# ESP32_Board.net
KiCad netlist of a schematic drawn in Altium Designer
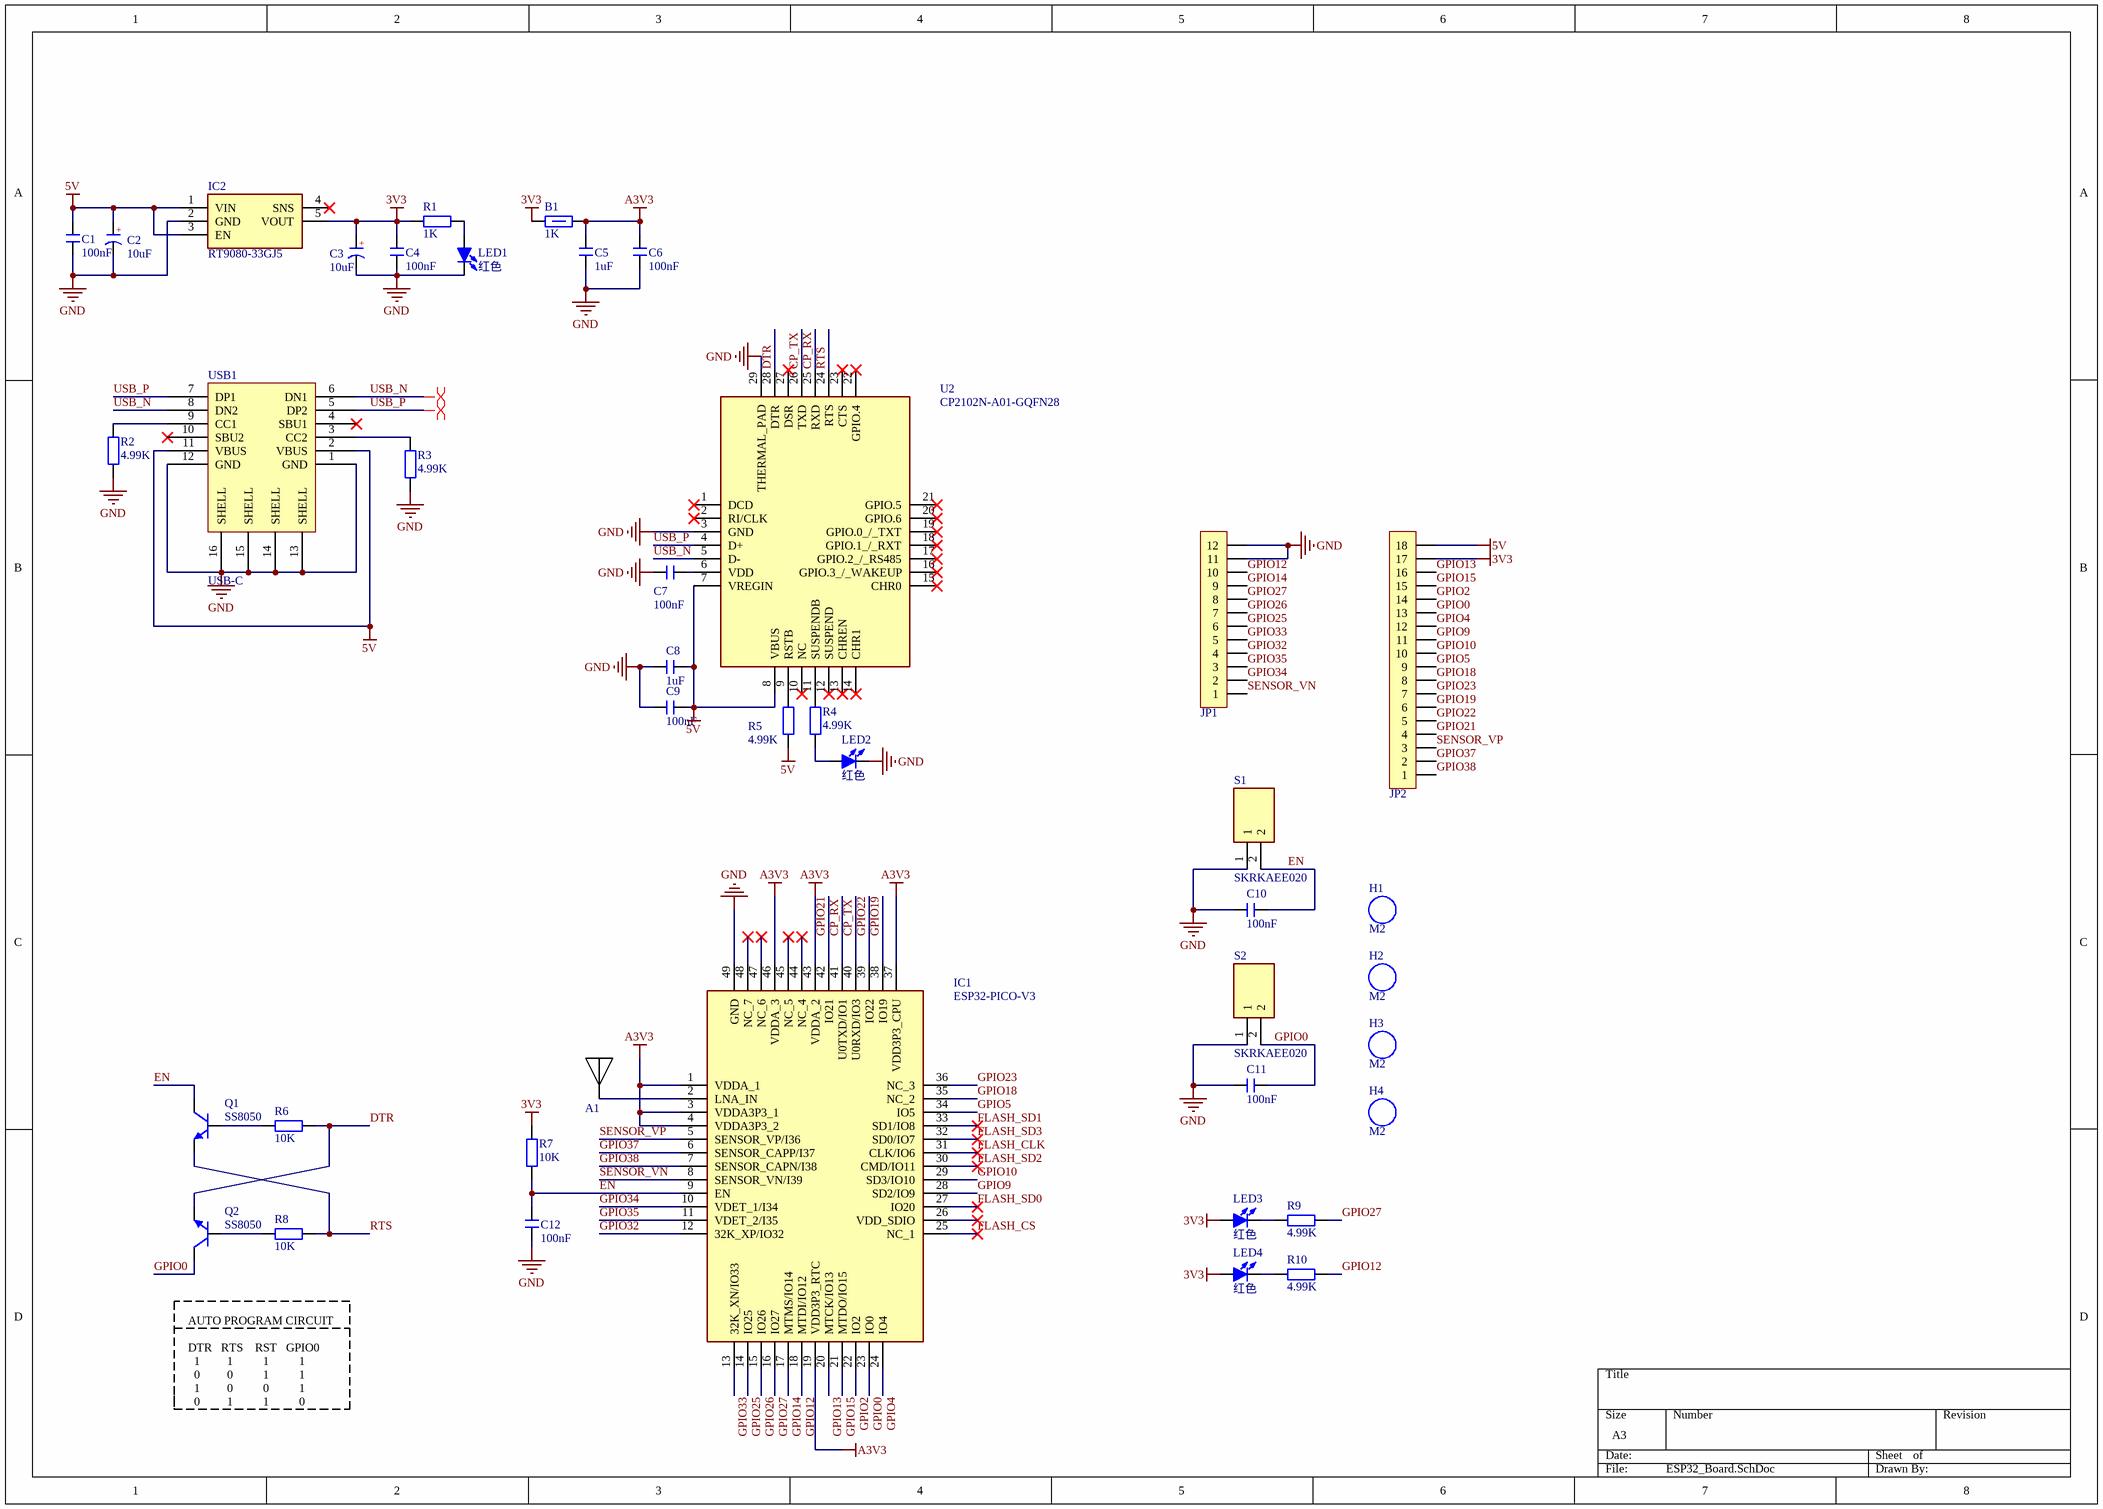
[diagram p0: ESP32_Board.SchDoc]

(export (version "E")
  (design (tool "Eeschema 10.0.6"))
  (components
    (comp (ref "A1")
      (value "RAINSUN")
      (footprint "ANT-Rainsun-AN5120")
      (description "陶瓷天线")
      (libsource (lib "14.1 - 天线") (part "ANT-Rainsun-AP5120"))
    )
    (comp (ref "B1")
      (value "1K")
      (footprint "B 0603_L")
      (description "贴片磁珠")
      (libsource (lib "3.1   - 电阻-电容-电感") (part "B"))
    )
    (comp (ref "C1")
      (value "100nF")
      (footprint "C 0603_L")
      (description "无极性贴片电容")
      (fields (field (name "版权归属") "源创客"))
      (libsource (lib "3.1   - 电阻-电容-电感") (part "C"))
    )
    (comp (ref "C2")
      (value "10uF")
      (footprint "CD A(3216)")
      (description "贴片钽电容")
      (fields (field (name "版权归属") "源创客"))
      (libsource (lib "3.1   - 电阻-电容-电感") (part "C-CD"))
    )
    (comp (ref "C3")
      (value "10uF")
      (footprint "CD A(3216)")
      (description "贴片钽电容")
      (fields (field (name "版权归属") "源创客"))
      (libsource (lib "3.1   - 电阻-电容-电感") (part "C-CD"))
    )
    (comp (ref "C4")
      (value "100nF")
      (footprint "C 0603_L")
      (description "无极性贴片电容")
      (fields (field (name "版权归属") "源创客"))
      (libsource (lib "3.1   - 电阻-电容-电感") (part "C"))
    )
    (comp (ref "C5")
      (value "1uF")
      (footprint "C 0603_L")
      (description "无极性贴片电容")
      (fields (field (name "版权归属") "源创客"))
      (libsource (lib "3.1   - 电阻-电容-电感") (part "C"))
    )
    (comp (ref "C6")
      (value "100nF")
      (footprint "C 0603_L")
      (description "无极性贴片电容")
      (fields (field (name "版权归属") "源创客"))
      (libsource (lib "3.1   - 电阻-电容-电感") (part "C"))
    )
    (comp (ref "C7")
      (value "100nF")
      (footprint "C 0603_L")
      (description "无极性贴片电容")
      (fields (field (name "版权归属") "源创客"))
      (libsource (lib "3.1   - 电阻-电容-电感") (part "C"))
    )
    (comp (ref "C8")
      (value "1uF")
      (footprint "C 0603_L")
      (description "无极性贴片电容")
      (fields (field (name "版权归属") "源创客"))
      (libsource (lib "3.1   - 电阻-电容-电感") (part "C"))
    )
    (comp (ref "C9")
      (value "100nF")
      (footprint "C 0603_L")
      (description "无极性贴片电容")
      (fields (field (name "版权归属") "源创客"))
      (libsource (lib "3.1   - 电阻-电容-电感") (part "C"))
    )
    (comp (ref "C10")
      (value "100nF")
      (footprint "C 0603_L")
      (description "无极性贴片电容")
      (fields (field (name "版权归属") "源创客"))
      (libsource (lib "3.1   - 电阻-电容-电感") (part "C"))
    )
    (comp (ref "C11")
      (value "100nF")
      (footprint "C 0603_L")
      (description "无极性贴片电容")
      (fields (field (name "版权归属") "源创客"))
      (libsource (lib "3.1   - 电阻-电容-电感") (part "C"))
    )
    (comp (ref "C12")
      (value "100nF")
      (footprint "C 0603_L")
      (description "无极性贴片电容")
      (fields (field (name "版权归属") "源创客"))
      (libsource (lib "3.1   - 电阻-电容-电感") (part "C"))
    )
    (comp (ref "H1")
      (value "M2")
      (footprint "M2 - 2.175")
      (description "铜柱孔")
      (fields (field (name "版权归属") "源创客"))
      (libsource (lib "15.1 - 未分类器件") (part "M2"))
    )
    (comp (ref "H2")
      (value "M2")
      (footprint "M2 - 2.175")
      (description "铜柱孔")
      (fields (field (name "版权归属") "源创客"))
      (libsource (lib "15.1 - 未分类器件") (part "M2"))
    )
    (comp (ref "H3")
      (value "M2")
      (footprint "M2 - 2.175")
      (description "铜柱孔")
      (fields (field (name "版权归属") "源创客"))
      (libsource (lib "15.1 - 未分类器件") (part "M2"))
    )
    (comp (ref "H4")
      (value "M2")
      (footprint "M2 - 2.175")
      (description "铜柱孔")
      (fields (field (name "版权归属") "源创客"))
      (libsource (lib "15.1 - 未分类器件") (part "M2"))
    )
    (comp (ref "IC1")
      (value "ESP32-PICO-V3")
      (footprint "SamacSys:ESP32PICOV3")
      (description "Integrated Circuit")
      (fields (field (name "MOUSER PART NUMBER") "356-ESP32-PICO-V3"))
      (libsource (lib "SamacSys") (part "ESP32-PICO-V3"))
    )
    (comp (ref "IC2")
      (value "RT9080-33GJ5")
      (footprint "SamacSys:SOT94P280X100-5N")
      (description "Integrated Circuit")
      (libsource (lib "*") (part "RT9080-33GJ5"))
    )
    (comp (ref "JP1")
      (value "HDR-1X12")
      (footprint "HDR2.54-LI-12P")
      (description "12P接插件")
      (fields (field (name "版权归属") "源创客"))
      (libsource (lib "4.5   - 接插件-脚距2.54") (part "Header 12"))
    )
    (comp (ref "JP2")
      (value "HDR-1X18")
      (footprint "HDR2.54-LI-18P")
      (description "18P接插件")
      (fields (field (name "版权归属") "源创客"))
      (libsource (lib "4.5   - 接插件-脚距2.54") (part "Header 18"))
    )
    (comp (ref "LED1")
      (value "红色")
      (footprint "LED 0603B")
      (description "贴片LED")
      (fields (field (name "版权归属") "源创客"))
      (libsource (lib "9.1   - LED") (part "LED-SMD"))
    )
    (comp (ref "LED2")
      (value "红色")
      (footprint "LED 0603B")
      (description "贴片LED")
      (fields (field (name "版权归属") "源创客"))
      (libsource (lib "9.1   - LED") (part "LED-SMD"))
    )
    (comp (ref "LED3")
      (value "红色")
      (footprint "LED 0603W")
      (description "贴片LED")
      (fields (field (name "版权归属") "源创客"))
      (libsource (lib "9.1   - LED") (part "LED-SMD"))
    )
    (comp (ref "LED4")
      (value "红色")
      (footprint "LED 0603W")
      (description "贴片LED")
      (fields (field (name "版权归属") "源创客"))
      (libsource (lib "9.1   - LED") (part "LED-SMD"))
    )
    (comp (ref "Q1")
      (value "SS8050")
      (footprint "SOT23-3N")
      (description "高频放大-NPN型")
      (fields (field (name "版权归属") "源创客"))
      (libsource (lib "6.2   - 三极管") (part "8050-SMD"))
    )
    (comp (ref "Q2")
      (value "SS8050")
      (footprint "SOT23-3N")
      (description "高频放大-NPN型")
      (fields (field (name "版权归属") "源创客"))
      (libsource (lib "6.2   - 三极管") (part "8050-SMD"))
    )
    (comp (ref "R1")
      (value "1K")
      (footprint "R 0603_L")
      (description "贴片电阻")
      (fields (field (name "版权归属") "源创客"))
      (libsource (lib "3.1   - 电阻-电容-电感") (part "R"))
    )
    (comp (ref "R2")
      (value "4.99K")
      (footprint "R 0603_L")
      (description "贴片电阻")
      (fields (field (name "版权归属") "源创客"))
      (libsource (lib "3.1   - 电阻-电容-电感") (part "R"))
    )
    (comp (ref "R3")
      (value "4.99K")
      (footprint "R 0603_L")
      (description "贴片电阻")
      (fields (field (name "版权归属") "源创客"))
      (libsource (lib "3.1   - 电阻-电容-电感") (part "R"))
    )
    (comp (ref "R4")
      (value "4.99K")
      (footprint "R 0603_L")
      (description "贴片电阻")
      (fields (field (name "版权归属") "源创客"))
      (libsource (lib "3.1   - 电阻-电容-电感") (part "R"))
    )
    (comp (ref "R5")
      (value "4.99K")
      (footprint "R 0603_L")
      (description "贴片电阻")
      (fields (field (name "版权归属") "源创客"))
      (libsource (lib "3.1   - 电阻-电容-电感") (part "R"))
    )
    (comp (ref "R6")
      (value "10K")
      (footprint "R 0603_L")
      (description "贴片电阻")
      (fields (field (name "版权归属") "源创客"))
      (libsource (lib "3.1   - 电阻-电容-电感") (part "R"))
    )
    (comp (ref "R7")
      (value "10K")
      (footprint "R 0603_L")
      (description "贴片电阻")
      (fields (field (name "版权归属") "源创客"))
      (libsource (lib "3.1   - 电阻-电容-电感") (part "R"))
    )
    (comp (ref "R8")
      (value "10K")
      (footprint "R 0603_L")
      (description "贴片电阻")
      (fields (field (name "版权归属") "源创客"))
      (libsource (lib "3.1   - 电阻-电容-电感") (part "R"))
    )
    (comp (ref "R9")
      (value "4.99K")
      (footprint "R 0603_L")
      (description "贴片电阻")
      (fields (field (name "版权归属") "源创客"))
      (libsource (lib "3.1   - 电阻-电容-电感") (part "R"))
    )
    (comp (ref "R10")
      (value "4.99K")
      (footprint "R 0603_L")
      (description "贴片电阻")
      (fields (field (name "版权归属") "源创客"))
      (libsource (lib "3.1   - 电阻-电容-电感") (part "R"))
    )
    (comp (ref "S1")
      (value "SKRKAEE020")
      (footprint "SamacSys:SKRKAEE020")
      (description "Switch")
      (fields (field (name "MOUSER PART NUMBER") "688-SKRKAEE020"))
      (libsource (lib "*") (part "SKRKAEE020"))
    )
    (comp (ref "S2")
      (value "SKRKAEE020")
      (footprint "SamacSys:SKRKAEE020")
      (description "Switch")
      (fields (field (name "MOUSER PART NUMBER") "688-SKRKAEE020"))
      (libsource (lib "*") (part "SKRKAEE020"))
    )
    (comp (ref "U2")
      (value "CP2102N-A01-GQFN28")
      (footprint "QFN28")
      (description "Integrated Circuit")
      (fields (field (name "MOUSER PART NUMBER") "634-CP2102NA01GQFN28"))
      (libsource (lib "*") (part "CP2102N-A01-GQFN28"))
    )
    (comp (ref "USB1")
      (value "USB-C")
      (footprint "USB-C-16")
      (description "USB-C型母接口")
      (fields (field (name "版权归属") "源创客"))
      (libsource (lib "4.1   - 接口类") (part "USB-C/16P"))
    )
  )
  (nets
    (net (code "1") (name "/CP_RX") (class "Default")
      (node (ref "IC1") (pin "41") (pinfunction "U0TXD/IO1_41") (pintype "passive"))
      (node (ref "U2") (pin "25") (pinfunction "RXD_25") (pintype "passive"))
    )
    (net (code "2") (name "/CP_TX") (class "Default")
      (node (ref "IC1") (pin "40") (pinfunction "U0RXD/IO3_40") (pintype "passive"))
      (node (ref "U2") (pin "26") (pinfunction "TXD_26") (pintype "passive"))
    )
    (net (code "3") (name "/DTR") (class "Default")
      (node (ref "Q2") (pin "2") (pinfunction "E_2") (pintype "passive"))
      (node (ref "R6") (pin "1") (pinfunction "1_1") (pintype "passive"))
      (node (ref "U2") (pin "28") (pinfunction "DTR_28") (pintype "passive"))
    )
    (net (code "4") (name "/EN") (class "Default")
      (node (ref "C10") (pin "1") (pinfunction "1_1") (pintype "passive"))
      (node (ref "C12") (pin "2") (pinfunction "2_2") (pintype "passive"))
      (node (ref "IC1") (pin "9") (pinfunction "EN_9") (pintype "passive"))
      (node (ref "Q1") (pin "3") (pinfunction "C_3") (pintype "passive"))
      (node (ref "R7") (pin "2") (pinfunction "2_2") (pintype "passive"))
      (node (ref "S1") (pin "2") (pinfunction "2_2") (pintype "passive"))
    )
    (net (code "5") (name "/FLASH_CLK") (class "Default")
      (node (ref "IC1") (pin "31") (pinfunction "CLK/IO6_31") (pintype "passive+no_connect"))
    )
    (net (code "6") (name "/FLASH_CS") (class "Default")
      (node (ref "IC1") (pin "25") (pinfunction "NC_1_25") (pintype "passive+no_connect"))
    )
    (net (code "7") (name "/FLASH_SD0") (class "Default")
      (node (ref "IC1") (pin "27") (pinfunction "IO20_27") (pintype "passive+no_connect"))
    )
    (net (code "8") (name "/FLASH_SD1") (class "Default")
      (node (ref "IC1") (pin "33") (pinfunction "SD1/IO8_33") (pintype "passive+no_connect"))
    )
    (net (code "9") (name "/FLASH_SD2") (class "Default")
      (node (ref "IC1") (pin "30") (pinfunction "CMD/IO11_30") (pintype "passive+no_connect"))
    )
    (net (code "10") (name "/FLASH_SD3") (class "Default")
      (node (ref "IC1") (pin "32") (pinfunction "SD0/IO7_32") (pintype "passive+no_connect"))
    )
    (net (code "11") (name "/GPIO0") (class "Default")
      (node (ref "C11") (pin "1") (pinfunction "1_1") (pintype "passive"))
      (node (ref "IC1") (pin "23") (pinfunction "IO0_23") (pintype "passive"))
      (node (ref "JP2") (pin "13") (pinfunction "13_13") (pintype "passive"))
      (node (ref "Q2") (pin "3") (pinfunction "C_3") (pintype "passive"))
      (node (ref "S2") (pin "2") (pinfunction "2_2") (pintype "passive"))
    )
    (net (code "12") (name "/GPIO2") (class "Default")
      (node (ref "IC1") (pin "22") (pinfunction "IO2_22") (pintype "passive"))
      (node (ref "JP2") (pin "14") (pinfunction "14_14") (pintype "passive"))
    )
    (net (code "13") (name "/GPIO4") (class "Default")
      (node (ref "IC1") (pin "24") (pinfunction "IO4_24") (pintype "passive"))
      (node (ref "JP2") (pin "12") (pinfunction "12_12") (pintype "passive"))
    )
    (net (code "14") (name "/GPIO5") (class "Default")
      (node (ref "IC1") (pin "34") (pinfunction "IO5_34") (pintype "passive"))
      (node (ref "JP2") (pin "9") (pinfunction "9_9") (pintype "passive"))
    )
    (net (code "15") (name "/GPIO9") (class "Default")
      (node (ref "IC1") (pin "28") (pinfunction "SD2/IO9_28") (pintype "passive"))
      (node (ref "JP2") (pin "11") (pinfunction "11_11") (pintype "passive"))
    )
    (net (code "16") (name "/GPIO10") (class "Default")
      (node (ref "IC1") (pin "29") (pinfunction "SD3/IO10_29") (pintype "passive"))
      (node (ref "JP2") (pin "10") (pinfunction "10_10") (pintype "passive"))
    )
    (net (code "17") (name "/GPIO12") (class "Default")
      (node (ref "IC1") (pin "18") (pinfunction "MTDI/IO12_18") (pintype "passive"))
      (node (ref "JP1") (pin "10") (pinfunction "10_10") (pintype "passive"))
      (node (ref "R10") (pin "1") (pinfunction "1_1") (pintype "passive"))
    )
    (net (code "18") (name "/GPIO13") (class "Default")
      (node (ref "IC1") (pin "20") (pinfunction "MTCK/IO13_20") (pintype "passive"))
      (node (ref "JP2") (pin "16") (pinfunction "16_16") (pintype "passive"))
    )
    (net (code "19") (name "/GPIO14") (class "Default")
      (node (ref "IC1") (pin "17") (pinfunction "MTMS/IO14_17") (pintype "passive"))
      (node (ref "JP1") (pin "9") (pinfunction "9_9") (pintype "passive"))
    )
    (net (code "20") (name "/GPIO15") (class "Default")
      (node (ref "IC1") (pin "21") (pinfunction "MTDO/IO15_21") (pintype "passive"))
      (node (ref "JP2") (pin "15") (pinfunction "15_15") (pintype "passive"))
    )
    (net (code "21") (name "/GPIO18") (class "Default")
      (node (ref "IC1") (pin "35") (pinfunction "NC_2_35") (pintype "passive"))
      (node (ref "JP2") (pin "8") (pinfunction "8_8") (pintype "passive"))
    )
    (net (code "22") (name "/GPIO19") (class "Default")
      (node (ref "IC1") (pin "38") (pinfunction "IO19_38") (pintype "passive"))
      (node (ref "JP2") (pin "6") (pinfunction "6_6") (pintype "passive"))
    )
    (net (code "23") (name "/GPIO21") (class "Default")
      (node (ref "IC1") (pin "42") (pinfunction "IO21_42") (pintype "passive"))
      (node (ref "JP2") (pin "4") (pinfunction "4_4") (pintype "passive"))
    )
    (net (code "24") (name "/GPIO22") (class "Default")
      (node (ref "IC1") (pin "39") (pinfunction "IO22_39") (pintype "passive"))
      (node (ref "JP2") (pin "5") (pinfunction "5_5") (pintype "passive"))
    )
    (net (code "25") (name "/GPIO23") (class "Default")
      (node (ref "IC1") (pin "36") (pinfunction "NC_3_36") (pintype "passive"))
      (node (ref "JP2") (pin "7") (pinfunction "7_7") (pintype "passive"))
    )
    (net (code "26") (name "/GPIO25") (class "Default")
      (node (ref "IC1") (pin "14") (pinfunction "IO25_14") (pintype "passive"))
      (node (ref "JP1") (pin "6") (pinfunction "6_6") (pintype "passive"))
    )
    (net (code "27") (name "/GPIO26") (class "Default")
      (node (ref "IC1") (pin "15") (pinfunction "IO26_15") (pintype "passive"))
      (node (ref "JP1") (pin "7") (pinfunction "7_7") (pintype "passive"))
    )
    (net (code "28") (name "/GPIO27") (class "Default")
      (node (ref "IC1") (pin "16") (pinfunction "IO27_16") (pintype "passive"))
      (node (ref "JP1") (pin "8") (pinfunction "8_8") (pintype "passive"))
      (node (ref "R9") (pin "1") (pinfunction "1_1") (pintype "passive"))
    )
    (net (code "29") (name "/GPIO32") (class "Default")
      (node (ref "IC1") (pin "12") (pinfunction "32K_XP/IO32_12") (pintype "passive"))
      (node (ref "JP1") (pin "4") (pinfunction "4_4") (pintype "passive"))
    )
    (net (code "30") (name "/GPIO33") (class "Default")
      (node (ref "IC1") (pin "13") (pinfunction "32K_XN/IO33_13") (pintype "passive"))
      (node (ref "JP1") (pin "5") (pinfunction "5_5") (pintype "passive"))
    )
    (net (code "31") (name "/GPIO34") (class "Default")
      (node (ref "IC1") (pin "10") (pinfunction "VDET_1/I34_10") (pintype "passive"))
      (node (ref "JP1") (pin "2") (pinfunction "2_2") (pintype "passive"))
    )
    (net (code "32") (name "/GPIO35") (class "Default")
      (node (ref "IC1") (pin "11") (pinfunction "VDET_2/I35_11") (pintype "passive"))
      (node (ref "JP1") (pin "3") (pinfunction "3_3") (pintype "passive"))
    )
    (net (code "33") (name "/GPIO37") (class "Default")
      (node (ref "IC1") (pin "6") (pinfunction "SENSOR_CAPP/I37_6") (pintype "passive"))
      (node (ref "JP2") (pin "2") (pinfunction "2_2") (pintype "passive"))
    )
    (net (code "34") (name "/GPIO38") (class "Default")
      (node (ref "IC1") (pin "7") (pinfunction "SENSOR_CAPN/I38_7") (pintype "passive"))
      (node (ref "JP2") (pin "1") (pinfunction "1_1") (pintype "passive"))
    )
    (net (code "35") (name "/RTS") (class "Default")
      (node (ref "Q1") (pin "2") (pinfunction "E_2") (pintype "passive"))
      (node (ref "R8") (pin "1") (pinfunction "1_1") (pintype "passive"))
      (node (ref "U2") (pin "24") (pinfunction "RTS_24") (pintype "passive"))
    )
    (net (code "36") (name "/SENSOR_VN") (class "Default")
      (node (ref "IC1") (pin "8") (pinfunction "SENSOR_VN/I39_8") (pintype "passive"))
      (node (ref "JP1") (pin "1") (pinfunction "1_1") (pintype "passive"))
    )
    (net (code "37") (name "/SENSOR_VP") (class "Default")
      (node (ref "IC1") (pin "5") (pinfunction "SENSOR_VP/I36_5") (pintype "passive"))
      (node (ref "JP2") (pin "3") (pinfunction "3_3") (pintype "passive"))
    )
    (net (code "38") (name "/USB_N") (class "Default")
      (node (ref "U2") (pin "5") (pinfunction "D-_5") (pintype "passive"))
      (node (ref "USB1") (pin "6") (pinfunction "DN1_6") (pintype "passive"))
      (node (ref "USB1") (pin "8") (pinfunction "DN2_8") (pintype "passive"))
    )
    (net (code "39") (name "/USB_P") (class "Default")
      (node (ref "U2") (pin "4") (pinfunction "D+_4") (pintype "passive"))
      (node (ref "USB1") (pin "5") (pinfunction "DP2_5") (pintype "passive"))
      (node (ref "USB1") (pin "7") (pinfunction "DP1_7") (pintype "passive"))
    )
    (net (code "40") (name "3V3") (class "Default")
      (node (ref "B1") (pin "2") (pinfunction "2_2") (pintype "passive"))
      (node (ref "C3") (pin "1") (pinfunction "A_1") (pintype "passive"))
      (node (ref "C4") (pin "2") (pinfunction "2_2") (pintype "passive"))
      (node (ref "IC2") (pin "5") (pinfunction "VOUT_5") (pintype "passive"))
      (node (ref "JP2") (pin "17") (pinfunction "17_17") (pintype "passive"))
      (node (ref "LED3") (pin "1") (pinfunction "A_1") (pintype "passive"))
      (node (ref "LED4") (pin "1") (pinfunction "A_1") (pintype "passive"))
      (node (ref "R1") (pin "2") (pinfunction "2_2") (pintype "passive"))
      (node (ref "R7") (pin "1") (pinfunction "1_1") (pintype "passive"))
    )
    (net (code "41") (name "5V") (class "Default")
      (node (ref "C1") (pin "2") (pinfunction "2_2") (pintype "passive"))
      (node (ref "C2") (pin "1") (pinfunction "A_1") (pintype "passive"))
      (node (ref "C8") (pin "1") (pinfunction "1_1") (pintype "passive"))
      (node (ref "C9") (pin "1") (pinfunction "1_1") (pintype "passive"))
      (node (ref "IC2") (pin "1") (pinfunction "VIN_1") (pintype "passive"))
      (node (ref "IC2") (pin "3") (pinfunction "EN_3") (pintype "passive"))
      (node (ref "JP2") (pin "18") (pinfunction "18_18") (pintype "passive"))
      (node (ref "R5") (pin "1") (pinfunction "1_1") (pintype "passive"))
      (node (ref "U2") (pin "7") (pinfunction "VREGIN_7") (pintype "passive"))
      (node (ref "U2") (pin "8") (pinfunction "VBUS_8") (pintype "passive"))
      (node (ref "USB1") (pin "11") (pinfunction "VBUS_11") (pintype "passive"))
      (node (ref "USB1") (pin "2") (pinfunction "VBUS_2") (pintype "passive"))
    )
    (net (code "42") (name "A3V3") (class "Default")
      (node (ref "B1") (pin "1") (pinfunction "1_1") (pintype "passive"))
      (node (ref "C5") (pin "2") (pinfunction "2_2") (pintype "passive"))
      (node (ref "C6") (pin "2") (pinfunction "2_2") (pintype "passive"))
      (node (ref "IC1") (pin "1") (pinfunction "VDDA_1_1") (pintype "passive"))
      (node (ref "IC1") (pin "19") (pinfunction "VDD3P3_RTC_19") (pintype "passive"))
      (node (ref "IC1") (pin "3") (pinfunction "VDDA3P3_1_3") (pintype "passive"))
      (node (ref "IC1") (pin "37") (pinfunction "VDD3P3_CPU_37") (pintype "passive"))
      (node (ref "IC1") (pin "4") (pinfunction "VDDA3P3_2_4") (pintype "passive"))
      (node (ref "IC1") (pin "43") (pinfunction "VDDA_2_43") (pintype "passive"))
      (node (ref "IC1") (pin "46") (pinfunction "VDDA_3_46") (pintype "passive"))
    )
    (net (code "43") (name "GND") (class "Default")
      (node (ref "C1") (pin "1") (pinfunction "1_1") (pintype "passive"))
      (node (ref "C10") (pin "2") (pinfunction "2_2") (pintype "passive"))
      (node (ref "C11") (pin "2") (pinfunction "2_2") (pintype "passive"))
      (node (ref "C12") (pin "1") (pinfunction "1_1") (pintype "passive"))
      (node (ref "C2") (pin "2") (pinfunction "K_2") (pintype "passive"))
      (node (ref "C3") (pin "2") (pinfunction "K_2") (pintype "passive"))
      (node (ref "C4") (pin "1") (pinfunction "1_1") (pintype "passive"))
      (node (ref "C5") (pin "1") (pinfunction "1_1") (pintype "passive"))
      (node (ref "C6") (pin "1") (pinfunction "1_1") (pintype "passive"))
      (node (ref "C7") (pin "2") (pinfunction "2_2") (pintype "passive"))
      (node (ref "C8") (pin "2") (pinfunction "2_2") (pintype "passive"))
      (node (ref "C9") (pin "2") (pinfunction "2_2") (pintype "passive"))
      (node (ref "IC1") (pin "49") (pinfunction "GND_49") (pintype "passive"))
      (node (ref "IC2") (pin "2") (pinfunction "GND_2") (pintype "passive"))
      (node (ref "JP1") (pin "11") (pinfunction "11_11") (pintype "passive"))
      (node (ref "JP1") (pin "12") (pinfunction "12_12") (pintype "passive"))
      (node (ref "LED1") (pin "2") (pinfunction "K_2") (pintype "passive"))
      (node (ref "LED2") (pin "2") (pinfunction "K_2") (pintype "passive"))
      (node (ref "R2") (pin "2") (pinfunction "2_2") (pintype "passive"))
      (node (ref "R3") (pin "2") (pinfunction "2_2") (pintype "passive"))
      (node (ref "S1") (pin "1") (pinfunction "1_1") (pintype "passive"))
      (node (ref "S2") (pin "1") (pinfunction "1_1") (pintype "passive"))
      (node (ref "U2") (pin "29") (pinfunction "THERMAL_PAD_29") (pintype "passive"))
      (node (ref "U2") (pin "3") (pinfunction "GND_3") (pintype "passive"))
      (node (ref "USB1") (pin "1") (pinfunction "GND_1") (pintype "passive"))
      (node (ref "USB1") (pin "12") (pinfunction "GND_12") (pintype "passive"))
      (node (ref "USB1") (pin "13") (pinfunction "SHELL_13") (pintype "passive"))
      (node (ref "USB1") (pin "14") (pinfunction "SHELL_14") (pintype "passive"))
      (node (ref "USB1") (pin "15") (pinfunction "SHELL_15") (pintype "passive"))
      (node (ref "USB1") (pin "16") (pinfunction "SHELL_16") (pintype "passive"))
    )
    (net (code "44") (name "Net-(IC1-LNA_IN)") (class "Default")
      (node (ref "A1") (pin "1") (pinfunction "1_1") (pintype "passive"))
      (node (ref "IC1") (pin "2") (pinfunction "LNA_IN_2") (pintype "passive"))
    )
    (net (code "45") (name "Net-(LED1-A)") (class "Default")
      (node (ref "LED1") (pin "1") (pinfunction "A_1") (pintype "passive"))
      (node (ref "R1") (pin "1") (pinfunction "1_1") (pintype "passive"))
    )
    (net (code "46") (name "Net-(LED2-A)") (class "Default")
      (node (ref "LED2") (pin "1") (pinfunction "A_1") (pintype "passive"))
      (node (ref "R4") (pin "1") (pinfunction "1_1") (pintype "passive"))
    )
    (net (code "47") (name "Net-(LED3-K)") (class "Default")
      (node (ref "LED3") (pin "2") (pinfunction "K_2") (pintype "passive"))
      (node (ref "R9") (pin "2") (pinfunction "2_2") (pintype "passive"))
    )
    (net (code "48") (name "Net-(LED4-K)") (class "Default")
      (node (ref "LED4") (pin "2") (pinfunction "K_2") (pintype "passive"))
      (node (ref "R10") (pin "2") (pinfunction "2_2") (pintype "passive"))
    )
    (net (code "49") (name "Net-(Q1-B)") (class "Default")
      (node (ref "Q1") (pin "1") (pinfunction "B_1") (pintype "passive"))
      (node (ref "R6") (pin "2") (pinfunction "2_2") (pintype "passive"))
    )
    (net (code "50") (name "Net-(Q2-B)") (class "Default")
      (node (ref "Q2") (pin "1") (pinfunction "B_1") (pintype "passive"))
      (node (ref "R8") (pin "2") (pinfunction "2_2") (pintype "passive"))
    )
    (net (code "51") (name "Net-(U2-RSTB)") (class "Default")
      (node (ref "R5") (pin "2") (pinfunction "2_2") (pintype "passive"))
      (node (ref "U2") (pin "9") (pinfunction "RSTB_9") (pintype "passive"))
    )
    (net (code "52") (name "Net-(U2-SUSPENDB)") (class "Default")
      (node (ref "R4") (pin "2") (pinfunction "2_2") (pintype "passive"))
      (node (ref "U2") (pin "11") (pinfunction "SUSPENDB_11") (pintype "passive"))
    )
    (net (code "53") (name "Net-(U2-VDD)") (class "Default")
      (node (ref "C7") (pin "1") (pinfunction "1_1") (pintype "passive"))
      (node (ref "U2") (pin "6") (pinfunction "VDD_6") (pintype "passive"))
    )
    (net (code "54") (name "Net-(USB1-CC1)") (class "Default")
      (node (ref "R2") (pin "1") (pinfunction "1_1") (pintype "passive"))
      (node (ref "USB1") (pin "9") (pinfunction "CC1_9") (pintype "passive"))
    )
    (net (code "55") (name "Net-(USB1-CC2)") (class "Default")
      (node (ref "R3") (pin "1") (pinfunction "1_1") (pintype "passive"))
      (node (ref "USB1") (pin "3") (pinfunction "CC2_3") (pintype "passive"))
    )
    (net (code "56") (name "unconnected-(IC1-NC_4-Pad44)") (class "Default")
      (node (ref "IC1") (pin "44") (pinfunction "NC_4_44") (pintype "passive+no_connect"))
    )
    (net (code "57") (name "unconnected-(IC1-NC_5-Pad45)") (class "Default")
      (node (ref "IC1") (pin "45") (pinfunction "NC_5_45") (pintype "passive+no_connect"))
    )
    (net (code "58") (name "unconnected-(IC1-NC_6-Pad47)") (class "Default")
      (node (ref "IC1") (pin "47") (pinfunction "NC_6_47") (pintype "passive+no_connect"))
    )
    (net (code "59") (name "unconnected-(IC1-NC_7-Pad48)") (class "Default")
      (node (ref "IC1") (pin "48") (pinfunction "NC_7_48") (pintype "passive+no_connect"))
    )
    (net (code "60") (name "unconnected-(IC1-VDD_SDIO-Pad26)") (class "Default")
      (node (ref "IC1") (pin "26") (pinfunction "VDD_SDIO_26") (pintype "passive+no_connect"))
    )
    (net (code "61") (name "unconnected-(IC2-SNS-Pad4)") (class "Default")
      (node (ref "IC2") (pin "4") (pinfunction "SNS_4") (pintype "passive+no_connect"))
    )
    (net (code "62") (name "unconnected-(U2-CHR0-Pad15)") (class "Default")
      (node (ref "U2") (pin "15") (pinfunction "CHR0_15") (pintype "passive+no_connect"))
    )
    (net (code "63") (name "unconnected-(U2-CHR1-Pad14)") (class "Default")
      (node (ref "U2") (pin "14") (pinfunction "CHR1_14") (pintype "passive+no_connect"))
    )
    (net (code "64") (name "unconnected-(U2-CHREN-Pad13)") (class "Default")
      (node (ref "U2") (pin "13") (pinfunction "CHREN_13") (pintype "passive+no_connect"))
    )
    (net (code "65") (name "unconnected-(U2-CTS-Pad23)") (class "Default")
      (node (ref "U2") (pin "23") (pinfunction "CTS_23") (pintype "passive+no_connect"))
    )
    (net (code "66") (name "unconnected-(U2-DCD-Pad1)") (class "Default")
      (node (ref "U2") (pin "1") (pinfunction "DCD_1") (pintype "passive+no_connect"))
    )
    (net (code "67") (name "unconnected-(U2-DSR-Pad27)") (class "Default")
      (node (ref "U2") (pin "27") (pinfunction "DSR_27") (pintype "passive+no_connect"))
    )
    (net (code "68") (name "unconnected-(U2-GPIO.0_{slash}_TXT-Pad19)") (class "Default")
      (node (ref "U2") (pin "19") (pinfunction "GPIO.0_/_TXT_19") (pintype "passive+no_connect"))
    )
    (net (code "69") (name "unconnected-(U2-GPIO.1_{slash}_RXT-Pad18)") (class "Default")
      (node (ref "U2") (pin "18") (pinfunction "GPIO.1_/_RXT_18") (pintype "passive+no_connect"))
    )
    (net (code "70") (name "unconnected-(U2-GPIO.2_{slash}_RS485-Pad17)") (class "Default")
      (node (ref "U2") (pin "17") (pinfunction "GPIO.2_/_RS485_17") (pintype "passive+no_connect"))
    )
    (net (code "71") (name "unconnected-(U2-GPIO.3_{slash}_WAKEUP-Pad16)") (class "Default")
      (node (ref "U2") (pin "16") (pinfunction "GPIO.3_/_WAKEUP_16") (pintype "passive+no_connect"))
    )
    (net (code "72") (name "unconnected-(U2-GPIO.4-Pad22)") (class "Default")
      (node (ref "U2") (pin "22") (pinfunction "GPIO.4_22") (pintype "passive+no_connect"))
    )
    (net (code "73") (name "unconnected-(U2-GPIO.5-Pad21)") (class "Default")
      (node (ref "U2") (pin "21") (pinfunction "GPIO.5_21") (pintype "passive+no_connect"))
    )
    (net (code "74") (name "unconnected-(U2-GPIO.6-Pad20)") (class "Default")
      (node (ref "U2") (pin "20") (pinfunction "GPIO.6_20") (pintype "passive+no_connect"))
    )
    (net (code "75") (name "unconnected-(U2-NC-Pad10)") (class "Default")
      (node (ref "U2") (pin "10") (pinfunction "NC_10") (pintype "passive+no_connect"))
    )
    (net (code "76") (name "unconnected-(U2-RI{slash}CLK-Pad2)") (class "Default")
      (node (ref "U2") (pin "2") (pinfunction "RI/CLK_2") (pintype "passive+no_connect"))
    )
    (net (code "77") (name "unconnected-(U2-SUSPEND-Pad12)") (class "Default")
      (node (ref "U2") (pin "12") (pinfunction "SUSPEND_12") (pintype "passive+no_connect"))
    )
    (net (code "78") (name "unconnected-(USB1-SBU1-Pad4)") (class "Default")
      (node (ref "USB1") (pin "4") (pinfunction "SBU1_4") (pintype "passive+no_connect"))
    )
    (net (code "79") (name "unconnected-(USB1-SBU2-Pad10)") (class "Default")
      (node (ref "USB1") (pin "10") (pinfunction "SBU2_10") (pintype "passive+no_connect"))
    )
  )
)
